# Hex-Inverter2.net
KiCad netlist of a schematic drawn in Altium Designer
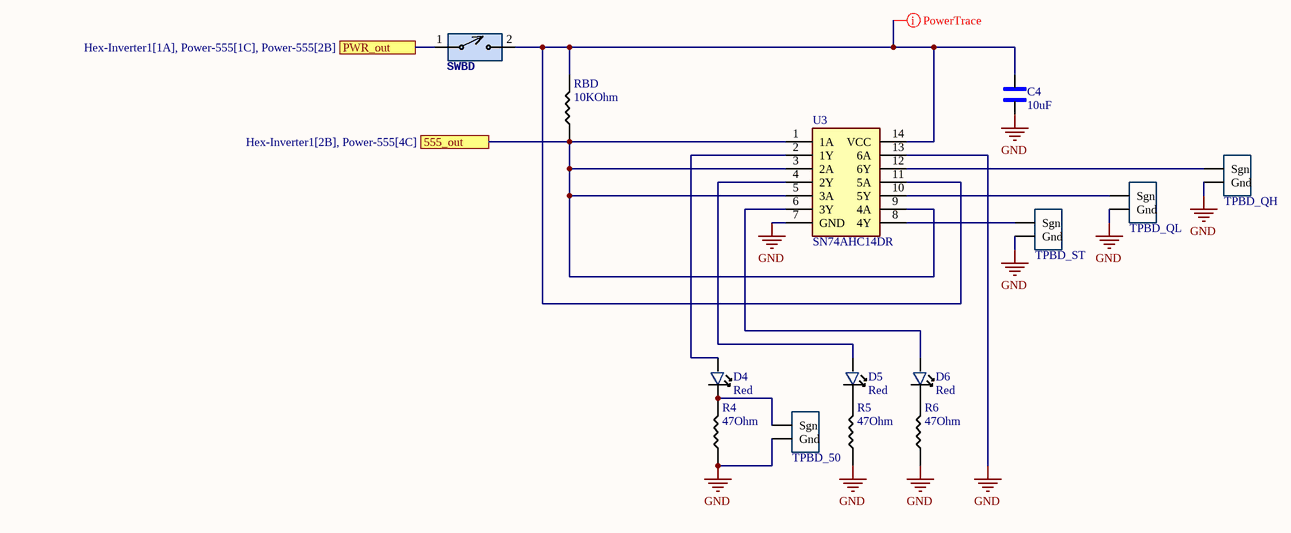
[diagram p0: Hex-Inverter2.SchDoc]

(export (version "E")
  (design (tool "Eeschema 10.0.6"))
  (components
    (comp (ref "C4")
      (value "10uF")
      (footprint "1206_Passive_Capacitor")
      (description "10uF ±10% 50V X5R 1206 Multilayer Ceramic Capacitors MLCC - SMD/SMT RoHS")
      (fields (field (name "LCSC PART#") "C13585") (field (name "MFR PART #") "CL31A106KBHNNNE"))
      (libsource (lib "ECEN5730Lib") (part "C_10uF_1206"))
    )
    (comp (ref "D4")
      (value "Red")
      (footprint "LED_1206")
      (description "Red 621~631nm 1206 Light Emitting Diodes (LED) RoHS")
      (fields (field (name "MFR PART #") "15-21/R6C-FQ1R1B/2T") (field (name "LCSC PART#") "C93133"))
      (libsource (lib "ECEN5730Lib") (part "LED_RED_1206"))
    )
    (comp (ref "D5")
      (value "Red")
      (footprint "LED_1206")
      (description "Red 621~631nm 1206 Light Emitting Diodes (LED) RoHS")
      (fields (field (name "MFR PART #") "15-21/R6C-FQ1R1B/2T") (field (name "LCSC PART#") "C93133"))
      (libsource (lib "ECEN5730Lib") (part "LED_RED_1206"))
    )
    (comp (ref "D6")
      (value "Red")
      (footprint "LED_1206")
      (description "Red 621~631nm 1206 Light Emitting Diodes (LED) RoHS")
      (fields (field (name "MFR PART #") "15-21/R6C-FQ1R1B/2T") (field (name "LCSC PART#") "C93133"))
      (libsource (lib "ECEN5730Lib") (part "LED_RED_1206"))
    )
    (comp (ref "R4")
      (value "47Ohm")
      (footprint "1206_Passive_Resitor")
      (description "47Ω ±5% 0.25W ±200ppm/℃ 1206 Chip Resistor - Surface Mount RoHS")
      (fields (field (name "MFR PART #") "1206W4J0470T5E") (field (name "LCSC PART#") "C25384"))
      (libsource (lib "ECEN5730Lib") (part "R_47Ohm_1206"))
    )
    (comp (ref "R5")
      (value "47Ohm")
      (footprint "1206_Passive_Resitor")
      (description "47Ω ±5% 0.25W ±200ppm/℃ 1206 Chip Resistor - Surface Mount RoHS")
      (fields (field (name "MFR PART #") "1206W4J0470T5E") (field (name "LCSC PART#") "C25384"))
      (libsource (lib "ECEN5730Lib") (part "R_47Ohm_1206"))
    )
    (comp (ref "R6")
      (value "47Ohm")
      (footprint "1206_Passive_Resitor")
      (description "47Ω ±5% 0.25W ±200ppm/℃ 1206 Chip Resistor - Surface Mount RoHS")
      (fields (field (name "MFR PART #") "1206W4J0470T5E") (field (name "LCSC PART#") "C25384"))
      (libsource (lib "ECEN5730Lib") (part "R_47Ohm_1206"))
    )
    (comp (ref "RBD")
      (value "10KOhm")
      (footprint "1206_Passive_Resitor")
      (description "10 kOhms ±5% 0.25W, 1/4W Chip Resistor 1206 (3216 Metric) Automotive AEC-Q200 Thick Film")
      (fields (field (name "MFR PART #") "RMCF1206FT10K0") (field (name "LCSC PART#") "C17902"))
      (libsource (lib "ECEN5730Lib") (part "R_10KOhm_1206"))
    )
    (comp (ref "SWBD")
      (value "SW_2Pin_100mil_Switch")
      (footprint "2Pin-Header-Conn")
      (description "2Pin Header")
      (fields (field (name "LCSC PART#") "C124375"))
      (libsource (lib "ECEN5730Lib") (part "SW_2Pin_100mil_Switch"))
    )
    (comp (ref "TPBD_50")
      (value "10x Probe TP")
      (footprint "TP10x_Probe")
      (description "Test Point 300 mil centers")
      (libsource (lib "ECEN5730Lib") (part "TP_10x_Probe"))
    )
    (comp (ref "TPBD_QH")
      (value "10x Probe TP")
      (footprint "TP10x_Probe")
      (description "Test Point 300 mil centers")
      (libsource (lib "ECEN5730Lib") (part "TP_10x_Probe"))
    )
    (comp (ref "TPBD_QL")
      (value "10x Probe TP")
      (footprint "TP10x_Probe")
      (description "Test Point 300 mil centers")
      (libsource (lib "ECEN5730Lib") (part "TP_10x_Probe"))
    )
    (comp (ref "TPBD_ST")
      (value "10x Probe TP")
      (footprint "TP10x_Probe")
      (description "Test Point 300 mil centers")
      (libsource (lib "ECEN5730Lib") (part "TP_10x_Probe"))
    )
    (comp (ref "U3")
      (value "SN74AHC14DR")
      (footprint "HEX_74AC14")
      (description "Inverter IC 6 Channel Schmitt Trigger 14-SOIC")
      (fields (field (name "LCSC PART#") "C6942"))
      (libsource (lib "ECEN5730Lib") (part "U_74AHC14"))
    )
  )
  (nets
    (net (code "1") (name "/555_out") (class "Default")
      (node (ref "RBD") (pin "1") (pinfunction "1_1") (pintype "passive"))
      (node (ref "U3") (pin "1") (pinfunction "1A_1") (pintype "passive"))
      (node (ref "U3") (pin "3") (pinfunction "2A_3") (pintype "passive"))
      (node (ref "U3") (pin "5") (pinfunction "3A_5") (pintype "passive"))
      (node (ref "U3") (pin "9") (pinfunction "4A_9") (pintype "passive"))
    )
    (net (code "2") (name "/PWR_out") (class "Default")
      (node (ref "SWBD") (pin "1") (pinfunction "1_1") (pintype "passive"))
    )
    (net (code "3") (name "GND") (class "Default")
      (node (ref "C4") (pin "1") (pinfunction "1_1") (pintype "passive"))
      (node (ref "R4") (pin "1") (pinfunction "1_1") (pintype "passive"))
      (node (ref "R5") (pin "1") (pinfunction "1_1") (pintype "passive"))
      (node (ref "R6") (pin "1") (pinfunction "1_1") (pintype "passive"))
      (node (ref "TPBD_50") (pin "2") (pinfunction "Gnd_2") (pintype "passive"))
      (node (ref "TPBD_QH") (pin "2") (pinfunction "Gnd_2") (pintype "passive"))
      (node (ref "TPBD_QL") (pin "2") (pinfunction "Gnd_2") (pintype "passive"))
      (node (ref "TPBD_ST") (pin "2") (pinfunction "Gnd_2") (pintype "passive"))
      (node (ref "U3") (pin "13") (pinfunction "6A_13") (pintype "passive"))
      (node (ref "U3") (pin "7") (pinfunction "GND_7") (pintype "passive"))
    )
    (net (code "4") (name "Net-(D5-Pad2)") (class "Default")
      (node (ref "D5") (pin "2") (pinfunction "2_2") (pintype "passive"))
      (node (ref "R5") (pin "2") (pinfunction "2_2") (pintype "passive"))
    )
    (net (code "5") (name "Net-(D6-Pad2)") (class "Default")
      (node (ref "D6") (pin "2") (pinfunction "2_2") (pintype "passive"))
      (node (ref "R6") (pin "2") (pinfunction "2_2") (pintype "passive"))
    )
    (net (code "6") (name "Net-(TPBD_50-Sgn)") (class "Default")
      (node (ref "D4") (pin "2") (pinfunction "2_2") (pintype "passive"))
      (node (ref "R4") (pin "2") (pinfunction "2_2") (pintype "passive"))
      (node (ref "TPBD_50") (pin "1") (pinfunction "Sgn_1") (pintype "passive"))
    )
    (net (code "7") (name "Net-(TPBD_QH-Sgn)") (class "Default")
      (node (ref "TPBD_QH") (pin "1") (pinfunction "Sgn_1") (pintype "passive"))
      (node (ref "U3") (pin "12") (pinfunction "6Y_12") (pintype "passive"))
    )
    (net (code "8") (name "Net-(TPBD_QL-Sgn)") (class "Default")
      (node (ref "TPBD_QL") (pin "1") (pinfunction "Sgn_1") (pintype "passive"))
      (node (ref "U3") (pin "10") (pinfunction "5Y_10") (pintype "passive"))
    )
    (net (code "9") (name "Net-(TPBD_ST-Sgn)") (class "Default")
      (node (ref "TPBD_ST") (pin "1") (pinfunction "Sgn_1") (pintype "passive"))
      (node (ref "U3") (pin "8") (pinfunction "4Y_8") (pintype "passive"))
    )
    (net (code "10") (name "Net-(U3-1Y)") (class "Default")
      (node (ref "D4") (pin "1") (pinfunction "1_1") (pintype "passive"))
      (node (ref "U3") (pin "2") (pinfunction "1Y_2") (pintype "passive"))
    )
    (net (code "11") (name "Net-(U3-2Y)") (class "Default")
      (node (ref "D5") (pin "1") (pinfunction "1_1") (pintype "passive"))
      (node (ref "U3") (pin "4") (pinfunction "2Y_4") (pintype "passive"))
    )
    (net (code "12") (name "Net-(U3-3Y)") (class "Default")
      (node (ref "D6") (pin "1") (pinfunction "1_1") (pintype "passive"))
      (node (ref "U3") (pin "6") (pinfunction "3Y_6") (pintype "passive"))
    )
    (net (code "13") (name "Net-(U3-5A)") (class "Default")
      (node (ref "C4") (pin "2") (pinfunction "2_2") (pintype "passive"))
      (node (ref "RBD") (pin "2") (pinfunction "2_2") (pintype "passive"))
      (node (ref "SWBD") (pin "2") (pinfunction "2_2") (pintype "passive"))
      (node (ref "U3") (pin "11") (pinfunction "5A_11") (pintype "passive"))
      (node (ref "U3") (pin "14") (pinfunction "VCC_14") (pintype "passive"))
    )
  )
)
